# killswitch.net
KiCad netlist of a schematic drawn in EAGLE
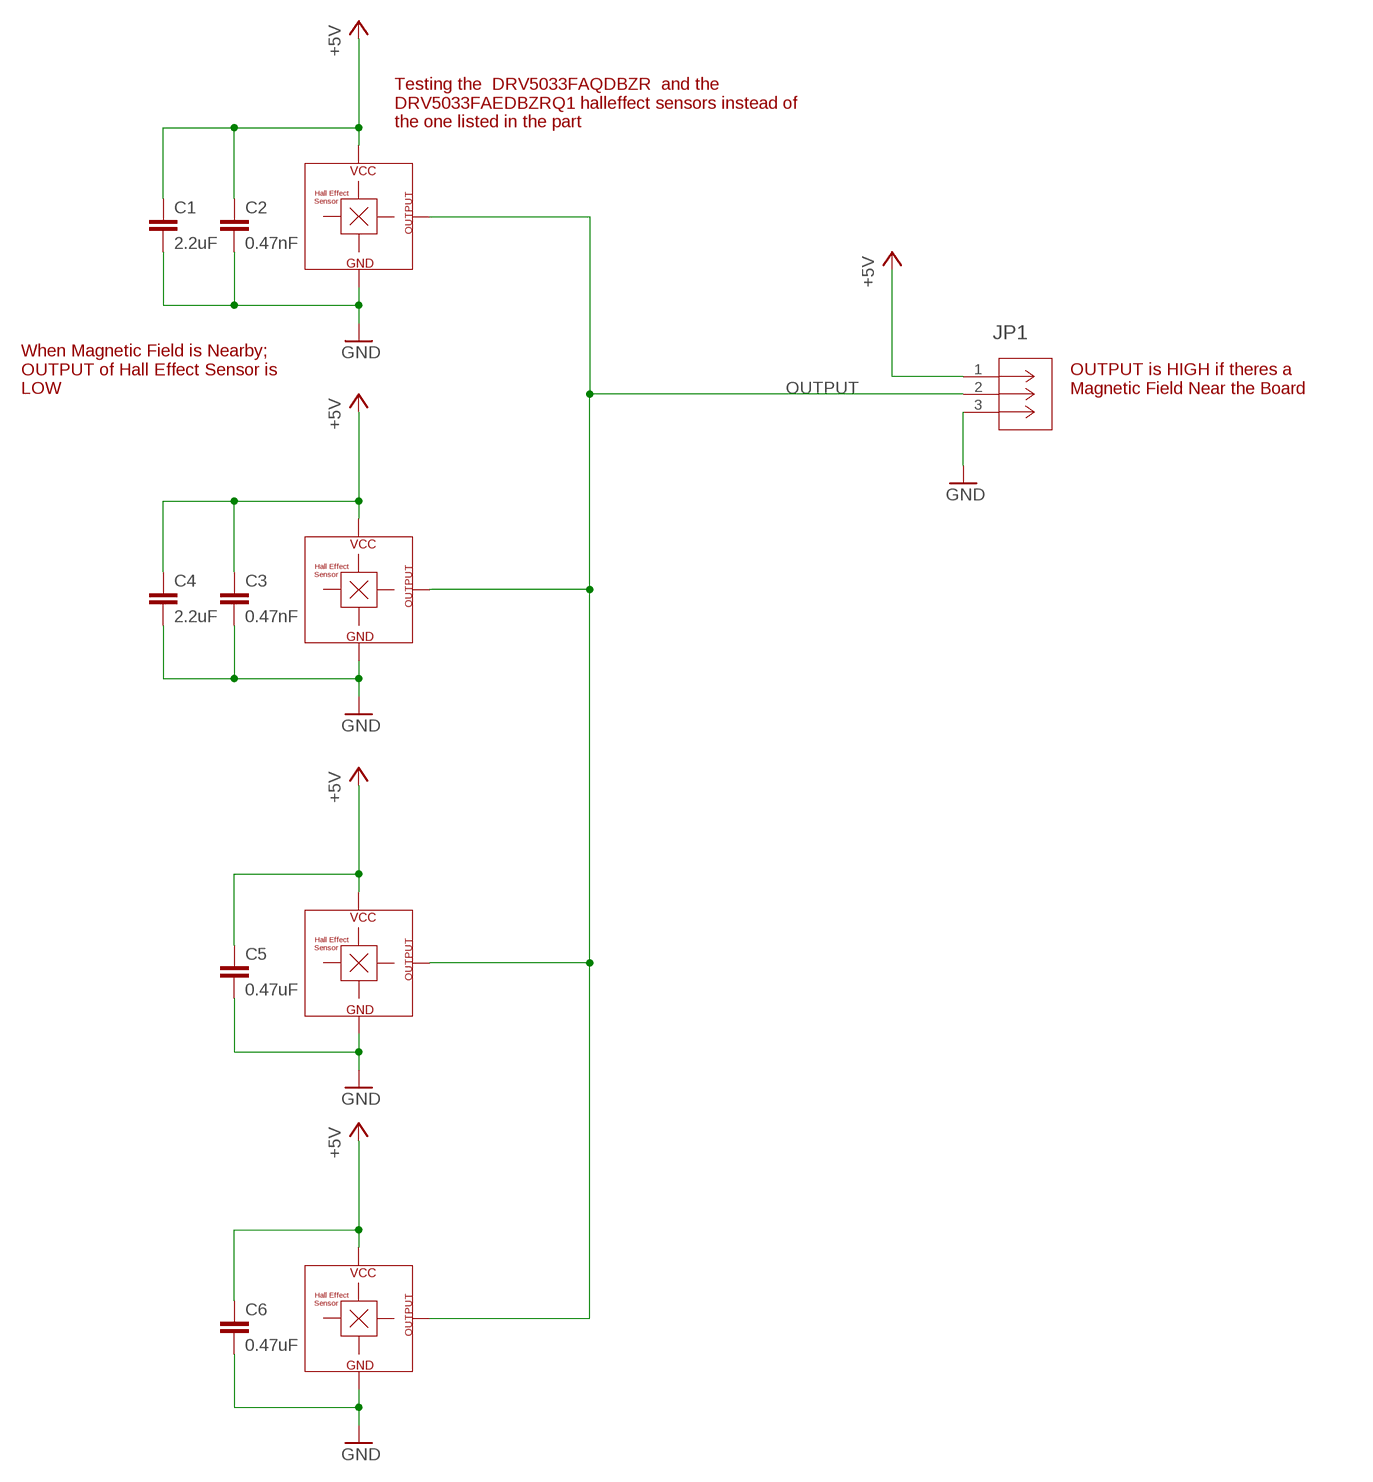
[diagram p0: schematic, sheet 1]

(export (version "E")
  (design (tool "Eeschema 10.0.6"))
  (components
    (comp (ref "C1")
      (value "2.2uF")
      (footprint "eagle-import:C0805")
      (libsource (lib "eagle-import") (part "C-EUC0805"))
    )
    (comp (ref "C2")
      (value "0.47nF")
      (footprint "eagle-import:C0603")
      (libsource (lib "eagle-import") (part "C-EUC0603"))
    )
    (comp (ref "C3")
      (value "0.47nF")
      (footprint "eagle-import:C0603")
      (libsource (lib "eagle-import") (part "C-EUC0603"))
    )
    (comp (ref "C4")
      (value "2.2uF")
      (footprint "eagle-import:C0805")
      (libsource (lib "eagle-import") (part "C-EUC0805"))
    )
    (comp (ref "C5")
      (value "0.47uF")
      (footprint "eagle-import:C0603")
      (libsource (lib "eagle-import") (part "C-EUC0603"))
    )
    (comp (ref "C6")
      (value "0.47uF")
      (footprint "eagle-import:C0603")
      (libsource (lib "eagle-import") (part "C-EUC0603"))
    )
    (comp (ref "JP1")
      (value "1241150-3")
      (footprint "eagle-import:CONN_1241150-3_TYCO")
      (fields (field (name "MANUFACTURER_PART_NUMBER") "12411503"))
      (libsource (lib "eagle-import") (part "1241150-3"))
    )
    (comp (ref "U$1")
      (value "TCS40DLR")
      (footprint "eagle-import:SOT23")
      (libsource (lib "eagle-import") (part "TCS40DLR"))
    )
    (comp (ref "U$3")
      (value "TCS40DLR")
      (footprint "eagle-import:SOT23")
      (libsource (lib "eagle-import") (part "TCS40DLR"))
    )
    (comp (ref "U$4")
      (value "TCS40DLR")
      (footprint "eagle-import:SOT23")
      (libsource (lib "eagle-import") (part "TCS40DLR"))
    )
    (comp (ref "U$5")
      (value "TCS40DLR")
      (footprint "eagle-import:SOT23")
      (libsource (lib "eagle-import") (part "TCS40DLR"))
    )
  )
  (nets
    (net (code "1") (name "+5V") (class "Default")
      (node (ref "C1") (pin "1") (pinfunction "1_1") (pintype "passive"))
      (node (ref "C2") (pin "1") (pinfunction "1_1") (pintype "passive"))
      (node (ref "C3") (pin "1") (pinfunction "1_1") (pintype "passive"))
      (node (ref "C4") (pin "1") (pinfunction "1_1") (pintype "passive"))
      (node (ref "C5") (pin "1") (pinfunction "1_1") (pintype "passive"))
      (node (ref "C6") (pin "1") (pinfunction "1_1") (pintype "passive"))
      (node (ref "JP1") (pin "1") (pinfunction "1_1") (pintype "passive"))
      (node (ref "U$1") (pin "VCC") (pinfunction "VCC_VCC") (pintype "bidirectional"))
      (node (ref "U$3") (pin "VCC") (pinfunction "VCC_VCC") (pintype "bidirectional"))
      (node (ref "U$4") (pin "VCC") (pinfunction "VCC_VCC") (pintype "bidirectional"))
      (node (ref "U$5") (pin "VCC") (pinfunction "VCC_VCC") (pintype "bidirectional"))
    )
    (net (code "2") (name "/OUTPUT") (class "Default")
      (node (ref "JP1") (pin "2") (pinfunction "2_2") (pintype "passive"))
      (node (ref "U$1") (pin "OUTPUT") (pinfunction "OUTPUT_OUTPUT") (pintype "bidirectional"))
      (node (ref "U$3") (pin "OUTPUT") (pinfunction "OUTPUT_OUTPUT") (pintype "bidirectional"))
      (node (ref "U$4") (pin "OUTPUT") (pinfunction "OUTPUT_OUTPUT") (pintype "bidirectional"))
      (node (ref "U$5") (pin "OUTPUT") (pinfunction "OUTPUT_OUTPUT") (pintype "bidirectional"))
    )
    (net (code "3") (name "GND") (class "Default")
      (node (ref "C1") (pin "2") (pinfunction "2_2") (pintype "passive"))
      (node (ref "C2") (pin "2") (pinfunction "2_2") (pintype "passive"))
      (node (ref "C3") (pin "2") (pinfunction "2_2") (pintype "passive"))
      (node (ref "C4") (pin "2") (pinfunction "2_2") (pintype "passive"))
      (node (ref "C5") (pin "2") (pinfunction "2_2") (pintype "passive"))
      (node (ref "C6") (pin "2") (pinfunction "2_2") (pintype "passive"))
      (node (ref "JP1") (pin "3") (pinfunction "3_3") (pintype "passive"))
      (node (ref "U$1") (pin "GND") (pinfunction "GND_GND") (pintype "bidirectional"))
      (node (ref "U$3") (pin "GND") (pinfunction "GND_GND") (pintype "bidirectional"))
      (node (ref "U$4") (pin "GND") (pinfunction "GND_GND") (pintype "bidirectional"))
      (node (ref "U$5") (pin "GND") (pinfunction "GND_GND") (pintype "bidirectional"))
    )
  )
)
